# PowerDissBoard.net
KiCad netlist of a schematic drawn in EAGLE
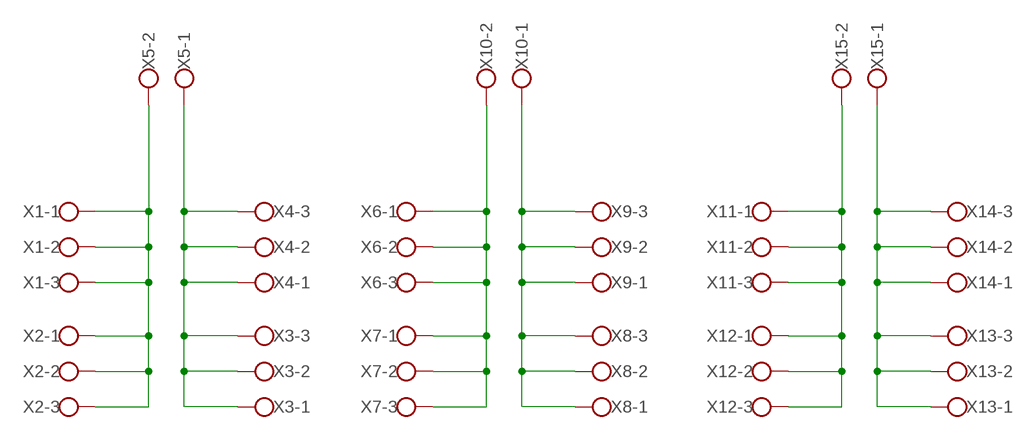
[diagram p0: schematic, sheet 1]

(export (version "E")
  (design (tool "Eeschema 10.0.6"))
  (components
    (comp (ref "X1")
      (value "W237-103")
      (footprint "eagle-import:W237-103")
      (fields (field (name "MPN") "237-103"))
      (libsource (lib "eagle-import") (part "W237-103"))
    )
    (comp (ref "X2")
      (value "W237-103")
      (footprint "eagle-import:W237-103")
      (fields (field (name "MPN") "237-103"))
      (libsource (lib "eagle-import") (part "W237-103"))
    )
    (comp (ref "X3")
      (value "W237-103")
      (footprint "eagle-import:W237-103")
      (fields (field (name "MPN") "237-103"))
      (libsource (lib "eagle-import") (part "W237-103"))
    )
    (comp (ref "X4")
      (value "W237-103")
      (footprint "eagle-import:W237-103")
      (fields (field (name "MPN") "237-103"))
      (libsource (lib "eagle-import") (part "W237-103"))
    )
    (comp (ref "X5")
      (value "W237-102")
      (footprint "eagle-import:W237-102")
      (fields (field (name "MPN") "237-102"))
      (libsource (lib "eagle-import") (part "W237-102"))
    )
    (comp (ref "X6")
      (value "W237-103")
      (footprint "eagle-import:W237-103")
      (fields (field (name "MPN") "237-103"))
      (libsource (lib "eagle-import") (part "W237-103"))
    )
    (comp (ref "X7")
      (value "W237-103")
      (footprint "eagle-import:W237-103")
      (fields (field (name "MPN") "237-103"))
      (libsource (lib "eagle-import") (part "W237-103"))
    )
    (comp (ref "X8")
      (value "W237-103")
      (footprint "eagle-import:W237-103")
      (fields (field (name "MPN") "237-103"))
      (libsource (lib "eagle-import") (part "W237-103"))
    )
    (comp (ref "X9")
      (value "W237-103")
      (footprint "eagle-import:W237-103")
      (fields (field (name "MPN") "237-103"))
      (libsource (lib "eagle-import") (part "W237-103"))
    )
    (comp (ref "X10")
      (value "W237-102")
      (footprint "eagle-import:W237-102")
      (fields (field (name "MPN") "237-102"))
      (libsource (lib "eagle-import") (part "W237-102"))
    )
    (comp (ref "X11")
      (value "W237-103")
      (footprint "eagle-import:W237-103")
      (fields (field (name "MPN") "237-103"))
      (libsource (lib "eagle-import") (part "W237-103"))
    )
    (comp (ref "X12")
      (value "W237-103")
      (footprint "eagle-import:W237-103")
      (fields (field (name "MPN") "237-103"))
      (libsource (lib "eagle-import") (part "W237-103"))
    )
    (comp (ref "X13")
      (value "W237-103")
      (footprint "eagle-import:W237-103")
      (fields (field (name "MPN") "237-103"))
      (libsource (lib "eagle-import") (part "W237-103"))
    )
    (comp (ref "X14")
      (value "W237-103")
      (footprint "eagle-import:W237-103")
      (fields (field (name "MPN") "237-103"))
      (libsource (lib "eagle-import") (part "W237-103"))
    )
    (comp (ref "X15")
      (value "W237-102")
      (footprint "eagle-import:W237-102")
      (fields (field (name "MPN") "237-102"))
      (libsource (lib "eagle-import") (part "W237-102"))
    )
  )
  (nets
    (net (code "1") (name "Net-(X1A-KL)") (class "Default")
      (node (ref "X1") (pin "1") (pinfunction "KL_1") (pintype "passive"))
      (node (ref "X1") (pin "2") (pinfunction "KL_2") (pintype "passive"))
      (node (ref "X1") (pin "3") (pinfunction "KL_3") (pintype "passive"))
      (node (ref "X2") (pin "1") (pinfunction "KL_1") (pintype "passive"))
      (node (ref "X2") (pin "2") (pinfunction "KL_2") (pintype "passive"))
      (node (ref "X2") (pin "3") (pinfunction "KL_3") (pintype "passive"))
      (node (ref "X5") (pin "2") (pinfunction "KL_2") (pintype "passive"))
    )
    (net (code "2") (name "Net-(X3A-KL)") (class "Default")
      (node (ref "X3") (pin "1") (pinfunction "KL_1") (pintype "passive"))
      (node (ref "X3") (pin "2") (pinfunction "KL_2") (pintype "passive"))
      (node (ref "X3") (pin "3") (pinfunction "KL_3") (pintype "passive"))
      (node (ref "X4") (pin "1") (pinfunction "KL_1") (pintype "passive"))
      (node (ref "X4") (pin "2") (pinfunction "KL_2") (pintype "passive"))
      (node (ref "X4") (pin "3") (pinfunction "KL_3") (pintype "passive"))
      (node (ref "X5") (pin "1") (pinfunction "KL_1") (pintype "passive"))
    )
    (net (code "3") (name "Net-(X10A-KL)") (class "Default")
      (node (ref "X10") (pin "1") (pinfunction "KL_1") (pintype "passive"))
      (node (ref "X8") (pin "1") (pinfunction "KL_1") (pintype "passive"))
      (node (ref "X8") (pin "2") (pinfunction "KL_2") (pintype "passive"))
      (node (ref "X8") (pin "3") (pinfunction "KL_3") (pintype "passive"))
      (node (ref "X9") (pin "1") (pinfunction "KL_1") (pintype "passive"))
      (node (ref "X9") (pin "2") (pinfunction "KL_2") (pintype "passive"))
      (node (ref "X9") (pin "3") (pinfunction "KL_3") (pintype "passive"))
    )
    (net (code "4") (name "Net-(X10B-KL)") (class "Default")
      (node (ref "X10") (pin "2") (pinfunction "KL_2") (pintype "passive"))
      (node (ref "X6") (pin "1") (pinfunction "KL_1") (pintype "passive"))
      (node (ref "X6") (pin "2") (pinfunction "KL_2") (pintype "passive"))
      (node (ref "X6") (pin "3") (pinfunction "KL_3") (pintype "passive"))
      (node (ref "X7") (pin "1") (pinfunction "KL_1") (pintype "passive"))
      (node (ref "X7") (pin "2") (pinfunction "KL_2") (pintype "passive"))
      (node (ref "X7") (pin "3") (pinfunction "KL_3") (pintype "passive"))
    )
    (net (code "5") (name "Net-(X11A-KL)") (class "Default")
      (node (ref "X11") (pin "1") (pinfunction "KL_1") (pintype "passive"))
      (node (ref "X11") (pin "2") (pinfunction "KL_2") (pintype "passive"))
      (node (ref "X11") (pin "3") (pinfunction "KL_3") (pintype "passive"))
      (node (ref "X12") (pin "1") (pinfunction "KL_1") (pintype "passive"))
      (node (ref "X12") (pin "2") (pinfunction "KL_2") (pintype "passive"))
      (node (ref "X12") (pin "3") (pinfunction "KL_3") (pintype "passive"))
      (node (ref "X15") (pin "2") (pinfunction "KL_2") (pintype "passive"))
    )
    (net (code "6") (name "Net-(X13A-KL)") (class "Default")
      (node (ref "X13") (pin "1") (pinfunction "KL_1") (pintype "passive"))
      (node (ref "X13") (pin "2") (pinfunction "KL_2") (pintype "passive"))
      (node (ref "X13") (pin "3") (pinfunction "KL_3") (pintype "passive"))
      (node (ref "X14") (pin "1") (pinfunction "KL_1") (pintype "passive"))
      (node (ref "X14") (pin "2") (pinfunction "KL_2") (pintype "passive"))
      (node (ref "X14") (pin "3") (pinfunction "KL_3") (pintype "passive"))
      (node (ref "X15") (pin "1") (pinfunction "KL_1") (pintype "passive"))
    )
  )
)
